# DMD-RaspberryPi.net
KiCad netlist of a schematic drawn in EAGLE
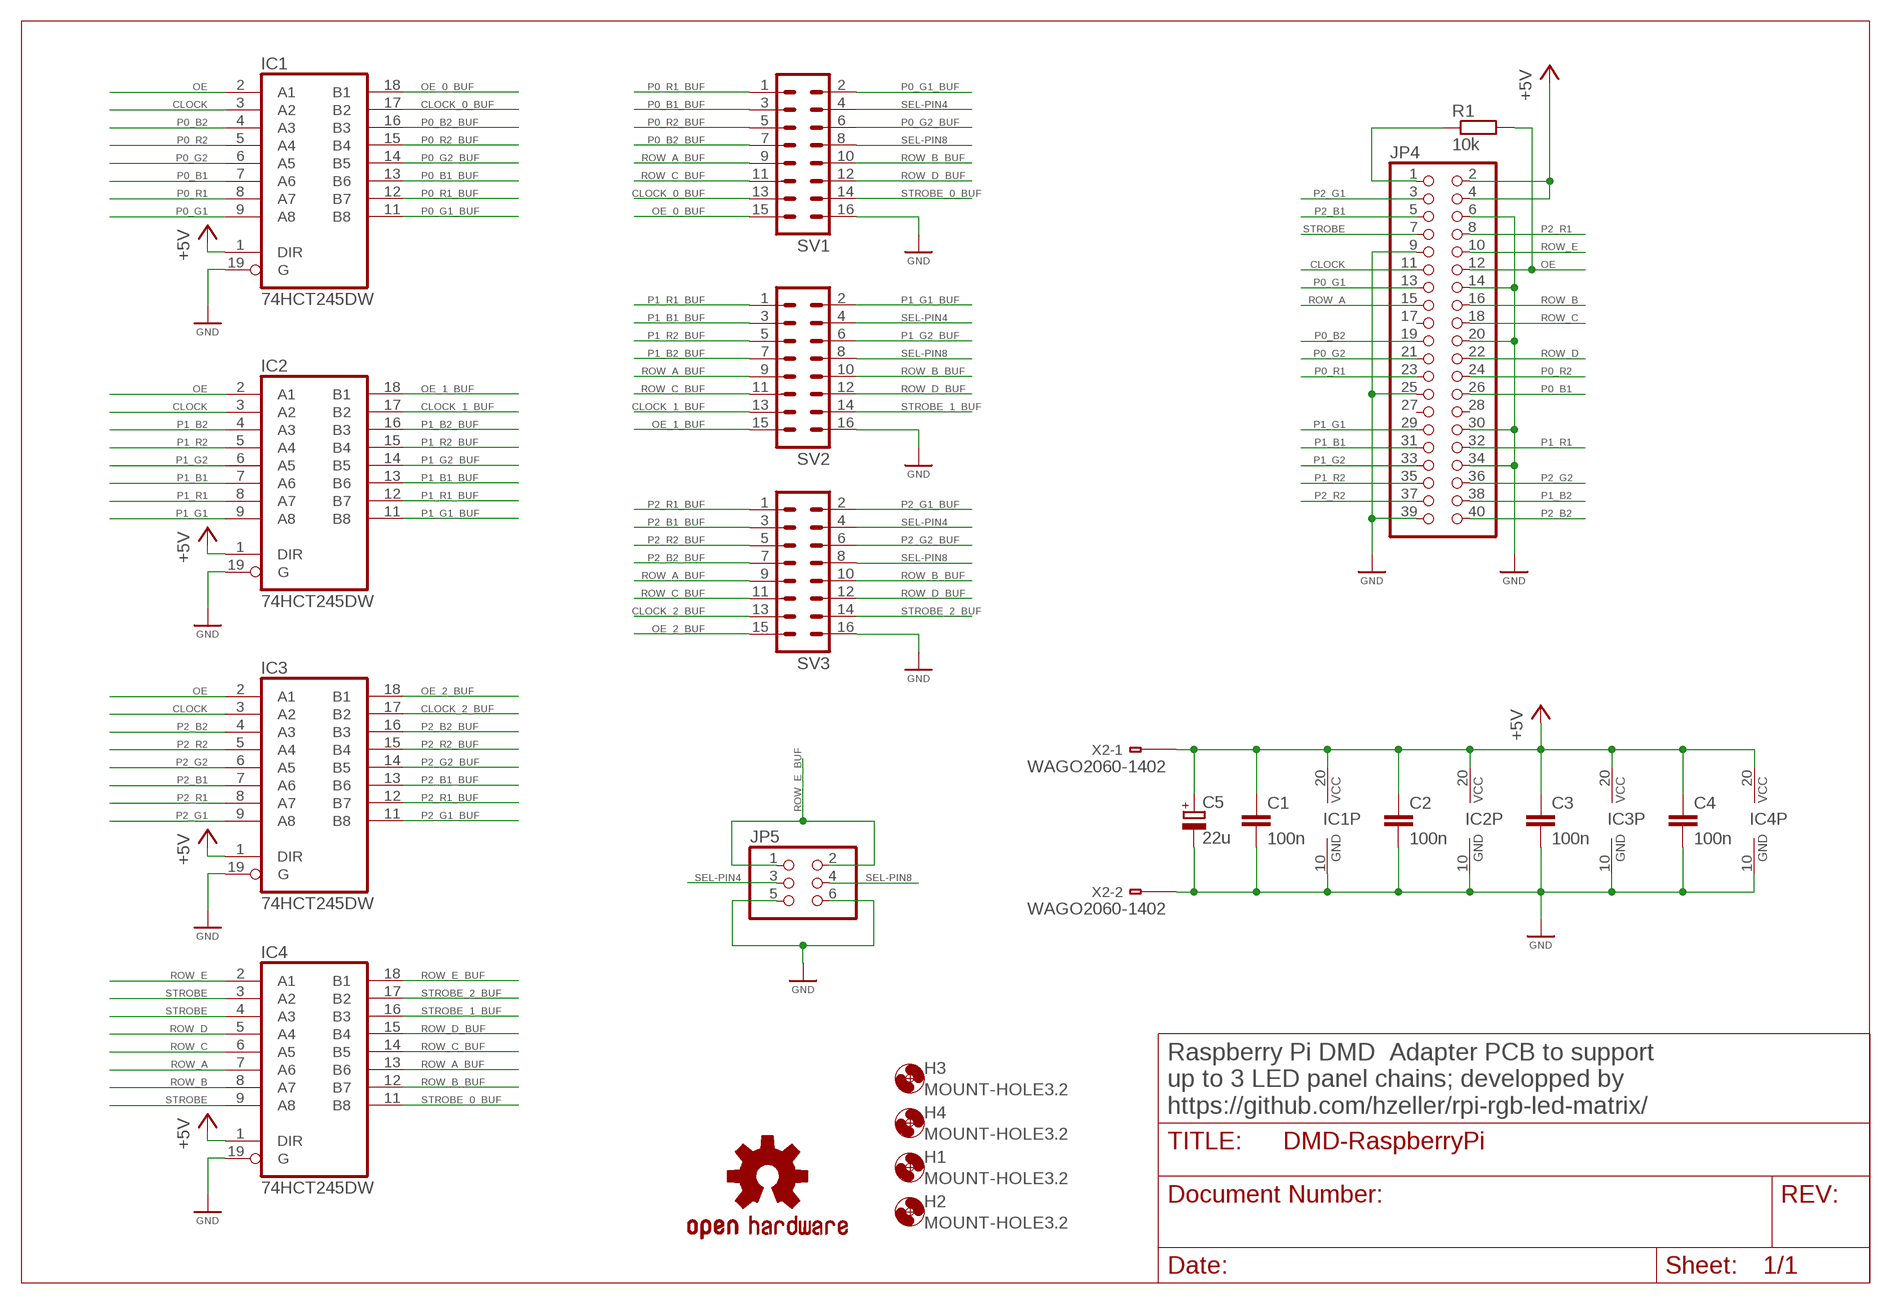
[diagram p0: schematic, sheet 1]

(export (version "E")
  (design (tool "Eeschema 10.0.6"))
  (components
    (comp (ref "C1")
      (value "100n")
      (footprint "eagle-import:C0805")
      (libsource (lib "eagle-import") (part "C-EUC0805"))
    )
    (comp (ref "C2")
      (value "100n")
      (footprint "eagle-import:C0805")
      (libsource (lib "eagle-import") (part "C-EUC0805"))
    )
    (comp (ref "C3")
      (value "100n")
      (footprint "eagle-import:C0805")
      (libsource (lib "eagle-import") (part "C-EUC0805"))
    )
    (comp (ref "C4")
      (value "100n")
      (footprint "eagle-import:C0805")
      (libsource (lib "eagle-import") (part "C-EUC0805"))
    )
    (comp (ref "C5")
      (value "22u")
      (footprint "eagle-import:PANASONIC_C")
      (libsource (lib "eagle-import") (part "CPOL-EUC"))
    )
    (comp (ref "H1")
      (value "MOUNT-HOLE3.2")
      (footprint "eagle-import:3,2")
      (libsource (lib "eagle-import") (part "MOUNT-HOLE3.2"))
    )
    (comp (ref "H2")
      (value "MOUNT-HOLE3.2")
      (footprint "eagle-import:3,2")
      (libsource (lib "eagle-import") (part "MOUNT-HOLE3.2"))
    )
    (comp (ref "H3")
      (value "MOUNT-HOLE3.2")
      (footprint "eagle-import:3,2")
      (libsource (lib "eagle-import") (part "MOUNT-HOLE3.2"))
    )
    (comp (ref "H4")
      (value "MOUNT-HOLE3.2")
      (footprint "eagle-import:3,2")
      (libsource (lib "eagle-import") (part "MOUNT-HOLE3.2"))
    )
    (comp (ref "IC1")
      (value "74HCT245DW")
      (footprint "eagle-import:SO20W")
      (libsource (lib "eagle-import") (part "74245DWHCT"))
    )
    (comp (ref "IC2")
      (value "74HCT245DW")
      (footprint "eagle-import:SO20W")
      (libsource (lib "eagle-import") (part "74245DWHCT"))
    )
    (comp (ref "IC3")
      (value "74HCT245DW")
      (footprint "eagle-import:SO20W")
      (libsource (lib "eagle-import") (part "74245DWHCT"))
    )
    (comp (ref "IC4")
      (value "74HCT245DW")
      (footprint "eagle-import:SO20W")
      (libsource (lib "eagle-import") (part "74245DWHCT"))
    )
    (comp (ref "JP4")
      (value "PINHD-2X20")
      (footprint "eagle-import:2X20")
      (libsource (lib "eagle-import") (part "PINHD-2X20"))
    )
    (comp (ref "JP5")
      (value "PINHD-2X3")
      (footprint "eagle-import:2X03")
      (libsource (lib "eagle-import") (part "PINHD-2X3"))
    )
    (comp (ref "LOGO1")
      (value "OSHW-LOGOL-COPPER")
      (footprint "eagle-import:OSHW-LOGO-L_COPPER")
      (libsource (lib "eagle-import") (part "OSHW-LOGOL-COPPER"))
    )
    (comp (ref "R1")
      (value "10k")
      (footprint "eagle-import:R0805")
      (libsource (lib "eagle-import") (part "R-EU_R0805"))
    )
    (comp (ref "SV1")
      (value "ML16")
      (footprint "eagle-import:ML16")
      (libsource (lib "eagle-import") (part "ML16"))
    )
    (comp (ref "SV2")
      (value "ML16")
      (footprint "eagle-import:ML16")
      (libsource (lib "eagle-import") (part "ML16"))
    )
    (comp (ref "SV3")
      (value "ML16")
      (footprint "eagle-import:ML16")
      (libsource (lib "eagle-import") (part "ML16"))
    )
    (comp (ref "X2")
      (value "WAGO2060-1402")
      (footprint "eagle-import:THT_RM4_2")
      (libsource (lib "eagle-import") (part "WAGO2060-1402"))
    )
  )
  (nets
    (net (code "1") (name "+5V") (class "Default")
      (node (ref "C1") (pin "1") (pinfunction "1_1") (pintype "passive"))
      (node (ref "C2") (pin "1") (pinfunction "1_1") (pintype "passive"))
      (node (ref "C3") (pin "1") (pinfunction "1_1") (pintype "passive"))
      (node (ref "C4") (pin "1") (pinfunction "1_1") (pintype "passive"))
      (node (ref "C5") (pin "+") (pinfunction "+_+") (pintype "passive"))
      (node (ref "IC1") (pin "1") (pinfunction "DIR_1") (pintype "input"))
      (node (ref "IC1") (pin "20") (pinfunction "VCC_20") (pintype "power_in"))
      (node (ref "IC2") (pin "1") (pinfunction "DIR_1") (pintype "input"))
      (node (ref "IC2") (pin "20") (pinfunction "VCC_20") (pintype "power_in"))
      (node (ref "IC3") (pin "1") (pinfunction "DIR_1") (pintype "input"))
      (node (ref "IC3") (pin "20") (pinfunction "VCC_20") (pintype "power_in"))
      (node (ref "IC4") (pin "1") (pinfunction "DIR_1") (pintype "input"))
      (node (ref "IC4") (pin "20") (pinfunction "VCC_20") (pintype "power_in"))
      (node (ref "JP4") (pin "2") (pinfunction "2_2") (pintype "passive"))
      (node (ref "JP4") (pin "4") (pinfunction "4_4") (pintype "passive"))
      (node (ref "X2") (pin "A2") (pinfunction "PIN_A2") (pintype "passive"))
    )
    (net (code "2") (name "/CLOCK") (class "Default")
      (node (ref "IC1") (pin "3") (pinfunction "A2_3") (pintype "bidirectional"))
      (node (ref "IC2") (pin "3") (pinfunction "A2_3") (pintype "bidirectional"))
      (node (ref "IC3") (pin "3") (pinfunction "A2_3") (pintype "bidirectional"))
      (node (ref "JP4") (pin "11") (pinfunction "11_11") (pintype "passive"))
    )
    (net (code "3") (name "/CLOCK_0_BUF") (class "Default")
      (node (ref "IC1") (pin "17") (pinfunction "B2_17") (pintype "bidirectional"))
      (node (ref "SV1") (pin "13") (pinfunction "13_13") (pintype "passive"))
    )
    (net (code "4") (name "/CLOCK_1_BUF") (class "Default")
      (node (ref "IC2") (pin "17") (pinfunction "B2_17") (pintype "bidirectional"))
      (node (ref "SV2") (pin "13") (pinfunction "13_13") (pintype "passive"))
    )
    (net (code "5") (name "/CLOCK_2_BUF") (class "Default")
      (node (ref "IC3") (pin "17") (pinfunction "B2_17") (pintype "bidirectional"))
      (node (ref "SV3") (pin "13") (pinfunction "13_13") (pintype "passive"))
    )
    (net (code "6") (name "/OE") (class "Default")
      (node (ref "IC1") (pin "2") (pinfunction "A1_2") (pintype "bidirectional"))
      (node (ref "IC2") (pin "2") (pinfunction "A1_2") (pintype "bidirectional"))
      (node (ref "IC3") (pin "2") (pinfunction "A1_2") (pintype "bidirectional"))
      (node (ref "JP4") (pin "12") (pinfunction "12_12") (pintype "passive"))
      (node (ref "R1") (pin "2") (pinfunction "2_2") (pintype "passive"))
    )
    (net (code "7") (name "/OE_0_BUF") (class "Default")
      (node (ref "IC1") (pin "18") (pinfunction "B1_18") (pintype "bidirectional"))
      (node (ref "SV1") (pin "15") (pinfunction "15_15") (pintype "passive"))
    )
    (net (code "8") (name "/OE_1_BUF") (class "Default")
      (node (ref "IC2") (pin "18") (pinfunction "B1_18") (pintype "bidirectional"))
      (node (ref "SV2") (pin "15") (pinfunction "15_15") (pintype "passive"))
    )
    (net (code "9") (name "/OE_2_BUF") (class "Default")
      (node (ref "IC3") (pin "18") (pinfunction "B1_18") (pintype "bidirectional"))
      (node (ref "SV3") (pin "15") (pinfunction "15_15") (pintype "passive"))
    )
    (net (code "10") (name "/P0_B1") (class "Default")
      (node (ref "IC1") (pin "7") (pinfunction "A6_7") (pintype "bidirectional"))
      (node (ref "JP4") (pin "26") (pinfunction "26_26") (pintype "passive"))
    )
    (net (code "11") (name "/P0_B1_BUF") (class "Default")
      (node (ref "IC1") (pin "13") (pinfunction "B6_13") (pintype "bidirectional"))
      (node (ref "SV1") (pin "3") (pinfunction "3_3") (pintype "passive"))
    )
    (net (code "12") (name "/P0_B2") (class "Default")
      (node (ref "IC1") (pin "4") (pinfunction "A3_4") (pintype "bidirectional"))
      (node (ref "JP4") (pin "19") (pinfunction "19_19") (pintype "passive"))
    )
    (net (code "13") (name "/P0_B2_BUF") (class "Default")
      (node (ref "IC1") (pin "16") (pinfunction "B3_16") (pintype "bidirectional"))
      (node (ref "SV1") (pin "7") (pinfunction "7_7") (pintype "passive"))
    )
    (net (code "14") (name "/P0_G1") (class "Default")
      (node (ref "IC1") (pin "9") (pinfunction "A8_9") (pintype "bidirectional"))
      (node (ref "JP4") (pin "13") (pinfunction "13_13") (pintype "passive"))
    )
    (net (code "15") (name "/P0_G1_BUF") (class "Default")
      (node (ref "IC1") (pin "11") (pinfunction "B8_11") (pintype "bidirectional"))
      (node (ref "SV1") (pin "2") (pinfunction "2_2") (pintype "passive"))
    )
    (net (code "16") (name "/P0_G2") (class "Default")
      (node (ref "IC1") (pin "6") (pinfunction "A5_6") (pintype "bidirectional"))
      (node (ref "JP4") (pin "21") (pinfunction "21_21") (pintype "passive"))
    )
    (net (code "17") (name "/P0_G2_BUF") (class "Default")
      (node (ref "IC1") (pin "14") (pinfunction "B5_14") (pintype "bidirectional"))
      (node (ref "SV1") (pin "6") (pinfunction "6_6") (pintype "passive"))
    )
    (net (code "18") (name "/P0_R1") (class "Default")
      (node (ref "IC1") (pin "8") (pinfunction "A7_8") (pintype "bidirectional"))
      (node (ref "JP4") (pin "23") (pinfunction "23_23") (pintype "passive"))
    )
    (net (code "19") (name "/P0_R1_BUF") (class "Default")
      (node (ref "IC1") (pin "12") (pinfunction "B7_12") (pintype "bidirectional"))
      (node (ref "SV1") (pin "1") (pinfunction "1_1") (pintype "passive"))
    )
    (net (code "20") (name "/P0_R2") (class "Default")
      (node (ref "IC1") (pin "5") (pinfunction "A4_5") (pintype "bidirectional"))
      (node (ref "JP4") (pin "24") (pinfunction "24_24") (pintype "passive"))
    )
    (net (code "21") (name "/P0_R2_BUF") (class "Default")
      (node (ref "IC1") (pin "15") (pinfunction "B4_15") (pintype "bidirectional"))
      (node (ref "SV1") (pin "5") (pinfunction "5_5") (pintype "passive"))
    )
    (net (code "22") (name "/P1_B1") (class "Default")
      (node (ref "IC2") (pin "7") (pinfunction "A6_7") (pintype "bidirectional"))
      (node (ref "JP4") (pin "31") (pinfunction "31_31") (pintype "passive"))
    )
    (net (code "23") (name "/P1_B1_BUF") (class "Default")
      (node (ref "IC2") (pin "13") (pinfunction "B6_13") (pintype "bidirectional"))
      (node (ref "SV2") (pin "3") (pinfunction "3_3") (pintype "passive"))
    )
    (net (code "24") (name "/P1_B2") (class "Default")
      (node (ref "IC2") (pin "4") (pinfunction "A3_4") (pintype "bidirectional"))
      (node (ref "JP4") (pin "38") (pinfunction "38_38") (pintype "passive"))
    )
    (net (code "25") (name "/P1_B2_BUF") (class "Default")
      (node (ref "IC2") (pin "16") (pinfunction "B3_16") (pintype "bidirectional"))
      (node (ref "SV2") (pin "7") (pinfunction "7_7") (pintype "passive"))
    )
    (net (code "26") (name "/P1_G1") (class "Default")
      (node (ref "IC2") (pin "9") (pinfunction "A8_9") (pintype "bidirectional"))
      (node (ref "JP4") (pin "29") (pinfunction "29_29") (pintype "passive"))
    )
    (net (code "27") (name "/P1_G1_BUF") (class "Default")
      (node (ref "IC2") (pin "11") (pinfunction "B8_11") (pintype "bidirectional"))
      (node (ref "SV2") (pin "2") (pinfunction "2_2") (pintype "passive"))
    )
    (net (code "28") (name "/P1_G2") (class "Default")
      (node (ref "IC2") (pin "6") (pinfunction "A5_6") (pintype "bidirectional"))
      (node (ref "JP4") (pin "33") (pinfunction "33_33") (pintype "passive"))
    )
    (net (code "29") (name "/P1_G2_BUF") (class "Default")
      (node (ref "IC2") (pin "14") (pinfunction "B5_14") (pintype "bidirectional"))
      (node (ref "SV2") (pin "6") (pinfunction "6_6") (pintype "passive"))
    )
    (net (code "30") (name "/P1_R1") (class "Default")
      (node (ref "IC2") (pin "8") (pinfunction "A7_8") (pintype "bidirectional"))
      (node (ref "JP4") (pin "32") (pinfunction "32_32") (pintype "passive"))
    )
    (net (code "31") (name "/P1_R1_BUF") (class "Default")
      (node (ref "IC2") (pin "12") (pinfunction "B7_12") (pintype "bidirectional"))
      (node (ref "SV2") (pin "1") (pinfunction "1_1") (pintype "passive"))
    )
    (net (code "32") (name "/P1_R2") (class "Default")
      (node (ref "IC2") (pin "5") (pinfunction "A4_5") (pintype "bidirectional"))
      (node (ref "JP4") (pin "35") (pinfunction "35_35") (pintype "passive"))
    )
    (net (code "33") (name "/P1_R2_BUF") (class "Default")
      (node (ref "IC2") (pin "15") (pinfunction "B4_15") (pintype "bidirectional"))
      (node (ref "SV2") (pin "5") (pinfunction "5_5") (pintype "passive"))
    )
    (net (code "34") (name "/P2_B1") (class "Default")
      (node (ref "IC3") (pin "7") (pinfunction "A6_7") (pintype "bidirectional"))
      (node (ref "JP4") (pin "5") (pinfunction "5_5") (pintype "passive"))
    )
    (net (code "35") (name "/P2_B1_BUF") (class "Default")
      (node (ref "IC3") (pin "13") (pinfunction "B6_13") (pintype "bidirectional"))
      (node (ref "SV3") (pin "3") (pinfunction "3_3") (pintype "passive"))
    )
    (net (code "36") (name "/P2_B2") (class "Default")
      (node (ref "IC3") (pin "4") (pinfunction "A3_4") (pintype "bidirectional"))
      (node (ref "JP4") (pin "40") (pinfunction "40_40") (pintype "passive"))
    )
    (net (code "37") (name "/P2_B2_BUF") (class "Default")
      (node (ref "IC3") (pin "16") (pinfunction "B3_16") (pintype "bidirectional"))
      (node (ref "SV3") (pin "7") (pinfunction "7_7") (pintype "passive"))
    )
    (net (code "38") (name "/P2_G1") (class "Default")
      (node (ref "IC3") (pin "9") (pinfunction "A8_9") (pintype "bidirectional"))
      (node (ref "JP4") (pin "3") (pinfunction "3_3") (pintype "passive"))
    )
    (net (code "39") (name "/P2_G1_BUF") (class "Default")
      (node (ref "IC3") (pin "11") (pinfunction "B8_11") (pintype "bidirectional"))
      (node (ref "SV3") (pin "2") (pinfunction "2_2") (pintype "passive"))
    )
    (net (code "40") (name "/P2_G2") (class "Default")
      (node (ref "IC3") (pin "6") (pinfunction "A5_6") (pintype "bidirectional"))
      (node (ref "JP4") (pin "36") (pinfunction "36_36") (pintype "passive"))
    )
    (net (code "41") (name "/P2_G2_BUF") (class "Default")
      (node (ref "IC3") (pin "14") (pinfunction "B5_14") (pintype "bidirectional"))
      (node (ref "SV3") (pin "6") (pinfunction "6_6") (pintype "passive"))
    )
    (net (code "42") (name "/P2_R1") (class "Default")
      (node (ref "IC3") (pin "8") (pinfunction "A7_8") (pintype "bidirectional"))
      (node (ref "JP4") (pin "8") (pinfunction "8_8") (pintype "passive"))
    )
    (net (code "43") (name "/P2_R1_BUF") (class "Default")
      (node (ref "IC3") (pin "12") (pinfunction "B7_12") (pintype "bidirectional"))
      (node (ref "SV3") (pin "1") (pinfunction "1_1") (pintype "passive"))
    )
    (net (code "44") (name "/P2_R2") (class "Default")
      (node (ref "IC3") (pin "5") (pinfunction "A4_5") (pintype "bidirectional"))
      (node (ref "JP4") (pin "37") (pinfunction "37_37") (pintype "passive"))
    )
    (net (code "45") (name "/P2_R2_BUF") (class "Default")
      (node (ref "IC3") (pin "15") (pinfunction "B4_15") (pintype "bidirectional"))
      (node (ref "SV3") (pin "5") (pinfunction "5_5") (pintype "passive"))
    )
    (net (code "46") (name "/ROW_A") (class "Default")
      (node (ref "IC4") (pin "7") (pinfunction "A6_7") (pintype "bidirectional"))
      (node (ref "JP4") (pin "15") (pinfunction "15_15") (pintype "passive"))
    )
    (net (code "47") (name "/ROW_A_BUF") (class "Default")
      (node (ref "IC4") (pin "13") (pinfunction "B6_13") (pintype "bidirectional"))
      (node (ref "SV1") (pin "9") (pinfunction "9_9") (pintype "passive"))
      (node (ref "SV2") (pin "9") (pinfunction "9_9") (pintype "passive"))
      (node (ref "SV3") (pin "9") (pinfunction "9_9") (pintype "passive"))
    )
    (net (code "48") (name "/ROW_B") (class "Default")
      (node (ref "IC4") (pin "8") (pinfunction "A7_8") (pintype "bidirectional"))
      (node (ref "JP4") (pin "16") (pinfunction "16_16") (pintype "passive"))
    )
    (net (code "49") (name "/ROW_B_BUF") (class "Default")
      (node (ref "IC4") (pin "12") (pinfunction "B7_12") (pintype "bidirectional"))
      (node (ref "SV1") (pin "10") (pinfunction "10_10") (pintype "passive"))
      (node (ref "SV2") (pin "10") (pinfunction "10_10") (pintype "passive"))
      (node (ref "SV3") (pin "10") (pinfunction "10_10") (pintype "passive"))
    )
    (net (code "50") (name "/ROW_C") (class "Default")
      (node (ref "IC4") (pin "6") (pinfunction "A5_6") (pintype "bidirectional"))
      (node (ref "JP4") (pin "18") (pinfunction "18_18") (pintype "passive"))
    )
    (net (code "51") (name "/ROW_C_BUF") (class "Default")
      (node (ref "IC4") (pin "14") (pinfunction "B5_14") (pintype "bidirectional"))
      (node (ref "SV1") (pin "11") (pinfunction "11_11") (pintype "passive"))
      (node (ref "SV2") (pin "11") (pinfunction "11_11") (pintype "passive"))
      (node (ref "SV3") (pin "11") (pinfunction "11_11") (pintype "passive"))
    )
    (net (code "52") (name "/ROW_D") (class "Default")
      (node (ref "IC4") (pin "5") (pinfunction "A4_5") (pintype "bidirectional"))
      (node (ref "JP4") (pin "22") (pinfunction "22_22") (pintype "passive"))
    )
    (net (code "53") (name "/ROW_D_BUF") (class "Default")
      (node (ref "IC4") (pin "15") (pinfunction "B4_15") (pintype "bidirectional"))
      (node (ref "SV1") (pin "12") (pinfunction "12_12") (pintype "passive"))
      (node (ref "SV2") (pin "12") (pinfunction "12_12") (pintype "passive"))
      (node (ref "SV3") (pin "12") (pinfunction "12_12") (pintype "passive"))
    )
    (net (code "54") (name "/ROW_E") (class "Default")
      (node (ref "IC4") (pin "2") (pinfunction "A1_2") (pintype "bidirectional"))
      (node (ref "JP4") (pin "10") (pinfunction "10_10") (pintype "passive"))
    )
    (net (code "55") (name "/ROW_E_BUF") (class "Default")
      (node (ref "IC4") (pin "18") (pinfunction "B1_18") (pintype "bidirectional"))
      (node (ref "JP5") (pin "1") (pinfunction "1_1") (pintype "passive"))
      (node (ref "JP5") (pin "2") (pinfunction "2_2") (pintype "passive"))
    )
    (net (code "56") (name "/SEL-PIN4") (class "Default")
      (node (ref "JP5") (pin "3") (pinfunction "3_3") (pintype "passive"))
      (node (ref "SV1") (pin "4") (pinfunction "4_4") (pintype "passive"))
      (node (ref "SV2") (pin "4") (pinfunction "4_4") (pintype "passive"))
      (node (ref "SV3") (pin "4") (pinfunction "4_4") (pintype "passive"))
    )
    (net (code "57") (name "/SEL-PIN8") (class "Default")
      (node (ref "JP5") (pin "4") (pinfunction "4_4") (pintype "passive"))
      (node (ref "SV1") (pin "8") (pinfunction "8_8") (pintype "passive"))
      (node (ref "SV2") (pin "8") (pinfunction "8_8") (pintype "passive"))
      (node (ref "SV3") (pin "8") (pinfunction "8_8") (pintype "passive"))
    )
    (net (code "58") (name "/STROBE") (class "Default")
      (node (ref "IC4") (pin "3") (pinfunction "A2_3") (pintype "bidirectional"))
      (node (ref "IC4") (pin "4") (pinfunction "A3_4") (pintype "bidirectional"))
      (node (ref "IC4") (pin "9") (pinfunction "A8_9") (pintype "bidirectional"))
      (node (ref "JP4") (pin "7") (pinfunction "7_7") (pintype "passive"))
    )
    (net (code "59") (name "/STROBE_0_BUF") (class "Default")
      (node (ref "IC4") (pin "11") (pinfunction "B8_11") (pintype "bidirectional"))
      (node (ref "SV1") (pin "14") (pinfunction "14_14") (pintype "passive"))
    )
    (net (code "60") (name "/STROBE_1_BUF") (class "Default")
      (node (ref "IC4") (pin "16") (pinfunction "B3_16") (pintype "bidirectional"))
      (node (ref "SV2") (pin "14") (pinfunction "14_14") (pintype "passive"))
    )
    (net (code "61") (name "/STROBE_2_BUF") (class "Default")
      (node (ref "IC4") (pin "17") (pinfunction "B2_17") (pintype "bidirectional"))
      (node (ref "SV3") (pin "14") (pinfunction "14_14") (pintype "passive"))
    )
    (net (code "62") (name "GND") (class "Default")
      (node (ref "C1") (pin "2") (pinfunction "2_2") (pintype "passive"))
      (node (ref "C2") (pin "2") (pinfunction "2_2") (pintype "passive"))
      (node (ref "C3") (pin "2") (pinfunction "2_2") (pintype "passive"))
      (node (ref "C4") (pin "2") (pinfunction "2_2") (pintype "passive"))
      (node (ref "C5") (pin "-") (pinfunction "-_-") (pintype "passive"))
      (node (ref "IC1") (pin "10") (pinfunction "GND_10") (pintype "power_in"))
      (node (ref "IC1") (pin "19") (pinfunction "G_19") (pintype "input"))
      (node (ref "IC2") (pin "10") (pinfunction "GND_10") (pintype "power_in"))
      (node (ref "IC2") (pin "19") (pinfunction "G_19") (pintype "input"))
      (node (ref "IC3") (pin "10") (pinfunction "GND_10") (pintype "power_in"))
      (node (ref "IC3") (pin "19") (pinfunction "G_19") (pintype "input"))
      (node (ref "IC4") (pin "10") (pinfunction "GND_10") (pintype "power_in"))
      (node (ref "IC4") (pin "19") (pinfunction "G_19") (pintype "input"))
      (node (ref "JP4") (pin "14") (pinfunction "14_14") (pintype "passive"))
      (node (ref "JP4") (pin "20") (pinfunction "20_20") (pintype "passive"))
      (node (ref "JP4") (pin "25") (pinfunction "25_25") (pintype "passive"))
      (node (ref "JP4") (pin "30") (pinfunction "30_30") (pintype "passive"))
      (node (ref "JP4") (pin "34") (pinfunction "34_34") (pintype "passive"))
      (node (ref "JP4") (pin "39") (pinfunction "39_39") (pintype "passive"))
      (node (ref "JP4") (pin "6") (pinfunction "6_6") (pintype "passive"))
      (node (ref "JP4") (pin "9") (pinfunction "9_9") (pintype "passive"))
      (node (ref "JP5") (pin "5") (pinfunction "5_5") (pintype "passive"))
      (node (ref "JP5") (pin "6") (pinfunction "6_6") (pintype "passive"))
      (node (ref "SV1") (pin "16") (pinfunction "16_16") (pintype "passive"))
      (node (ref "SV2") (pin "16") (pinfunction "16_16") (pintype "passive"))
      (node (ref "SV3") (pin "16") (pinfunction "16_16") (pintype "passive"))
      (node (ref "X2") (pin "B2") (pinfunction "PIN_B2") (pintype "passive"))
    )
    (net (code "63") (name "Net-(JP4-Pad1)") (class "Default")
      (node (ref "JP4") (pin "1") (pinfunction "1_1") (pintype "passive"))
      (node (ref "R1") (pin "1") (pinfunction "1_1") (pintype "passive"))
    )
    (net (code "64") (name "unconnected-(JP4-Pad17)") (class "Default")
      (node (ref "JP4") (pin "17") (pinfunction "17_17") (pintype "passive"))
    )
    (net (code "65") (name "unconnected-(JP4-Pad27)") (class "Default")
      (node (ref "JP4") (pin "27") (pinfunction "27_27") (pintype "passive"))
    )
    (net (code "66") (name "unconnected-(JP4-Pad28)") (class "Default")
      (node (ref "JP4") (pin "28") (pinfunction "28_28") (pintype "passive"))
    )
    (net (code "67") (name "unconnected-(X2A-PIN-PadA1)") (class "Default")
      (node (ref "X2") (pin "A1") (pinfunction "PIN_A1") (pintype "passive"))
    )
    (net (code "68") (name "unconnected-(X2B-PIN-PadB1)") (class "Default")
      (node (ref "X2") (pin "B1") (pinfunction "PIN_B1") (pintype "passive"))
    )
  )
)
